# Vehicle_Kill_Switch_Wiring.net
KiCad netlist of a schematic drawn in EAGLE
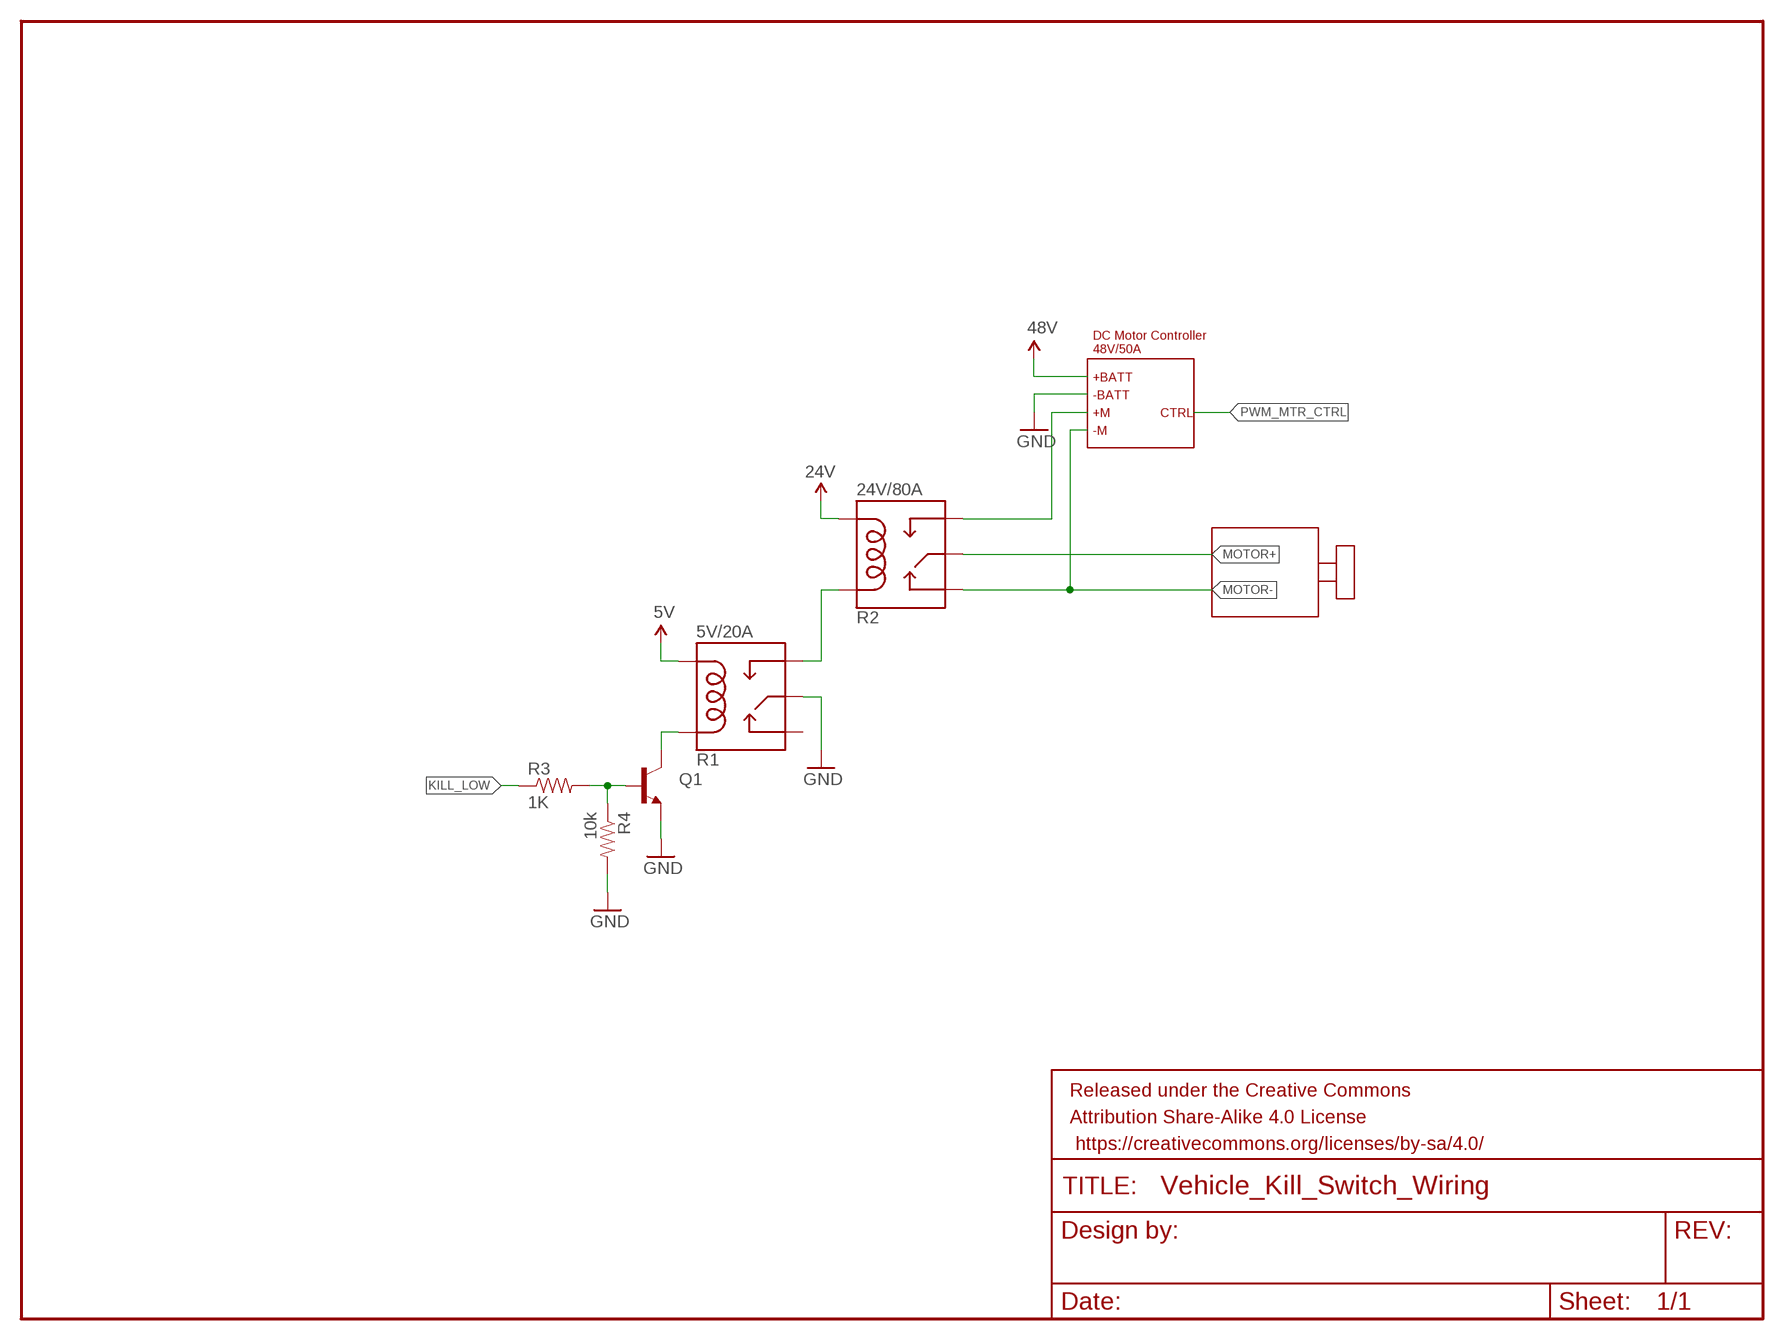
[diagram p0: schematic, sheet 1]

(export (version "E")
  (design (tool "Eeschema 10.0.6"))
  (components
    (comp (ref "FRAME1")
      (value "FRAME-LETTER")
      (footprint "eagle-import:CREATIVE_COMMONS")
      (libsource (lib "eagle-import") (part "FRAME-LETTER"))
    )
    (comp (ref "Q1")
      (value "TRANSISTOR_NPN2N3904")
      (footprint "eagle-import:TO-92")
      (libsource (lib "eagle-import") (part "TRANSISTOR_NPN2N3904"))
    )
    (comp (ref "R1")
      (value "5V/20A")
      (footprint "eagle-import:RELAY-G5Q")
      (libsource (lib "eagle-import") (part "RELAYPTH"))
    )
    (comp (ref "R2")
      (value "24V/80A")
      (footprint "eagle-import:RELAY-G5Q")
      (libsource (lib "eagle-import") (part "RELAYPTH"))
    )
    (comp (ref "R3")
      (value "1K")
      (footprint "eagle-import:AXIAL-0.3")
      (libsource (lib "eagle-import") (part "1KOHM-1/4W-1%(PTH)"))
    )
    (comp (ref "R4")
      (value "10k")
      (footprint "eagle-import:AXIAL-0.3")
      (libsource (lib "eagle-import") (part "10KOHM-1/4W-1%(PTH)HORIZ"))
    )
  )
  (nets
    (net (code "1") (name "5V") (class "Default")
      (node (ref "R1") (pin "1") (pinfunction "COIL2_1") (pintype "bidirectional"))
    )
    (net (code "2") (name "24V") (class "Default")
      (node (ref "R2") (pin "1") (pinfunction "COIL2_1") (pintype "bidirectional"))
    )
    (net (code "4") (name "GND") (class "Default")
      (node (ref "Q1") (pin "1") (pinfunction "E_1") (pintype "passive"))
      (node (ref "R1") (pin "2") (pinfunction "MAIN_2") (pintype "bidirectional"))
      (node (ref "R4") (pin "P$2") (pinfunction "2_P$2") (pintype "passive"))
    )
    (net (code "5") (name "KILL_LOW") (class "Default")
      (node (ref "R3") (pin "P$1") (pinfunction "1_P$1") (pintype "passive"))
    )
    (net (code "6") (name "MOTOR+") (class "Default")
      (node (ref "R2") (pin "2") (pinfunction "MAIN_2") (pintype "bidirectional"))
    )
    (net (code "7") (name "MOTOR-") (class "Default")
      (node (ref "R2") (pin "4") (pinfunction "NC_4") (pintype "bidirectional"))
    )
    (net (code "8") (name "Net-(Q1-B)") (class "Default")
      (node (ref "Q1") (pin "2") (pinfunction "B_2") (pintype "passive"))
      (node (ref "R3") (pin "P$2") (pinfunction "2_P$2") (pintype "passive"))
      (node (ref "R4") (pin "P$1") (pinfunction "1_P$1") (pintype "passive"))
    )
    (net (code "9") (name "Net-(Q1-C)") (class "Default")
      (node (ref "Q1") (pin "3") (pinfunction "C_3") (pintype "passive"))
      (node (ref "R1") (pin "5") (pinfunction "COIL1_5") (pintype "bidirectional"))
    )
    (net (code "10") (name "Net-(R1-NO)") (class "Default")
      (node (ref "R1") (pin "3") (pinfunction "NO_3") (pintype "bidirectional"))
      (node (ref "R2") (pin "5") (pinfunction "COIL1_5") (pintype "bidirectional"))
    )
    (net (code "12") (name "unconnected-(R1-NC-Pad4)") (class "Default")
      (node (ref "R1") (pin "4") (pinfunction "NC_4") (pintype "bidirectional"))
    )
    (net (code "13") (name "unconnected-(R2-NO-Pad3)") (class "Default")
      (node (ref "R2") (pin "3") (pinfunction "NO_3") (pintype "bidirectional"))
    )
  )
)
